# UpTo11_FrontPanel.net
KiCad netlist of a schematic drawn in EAGLE
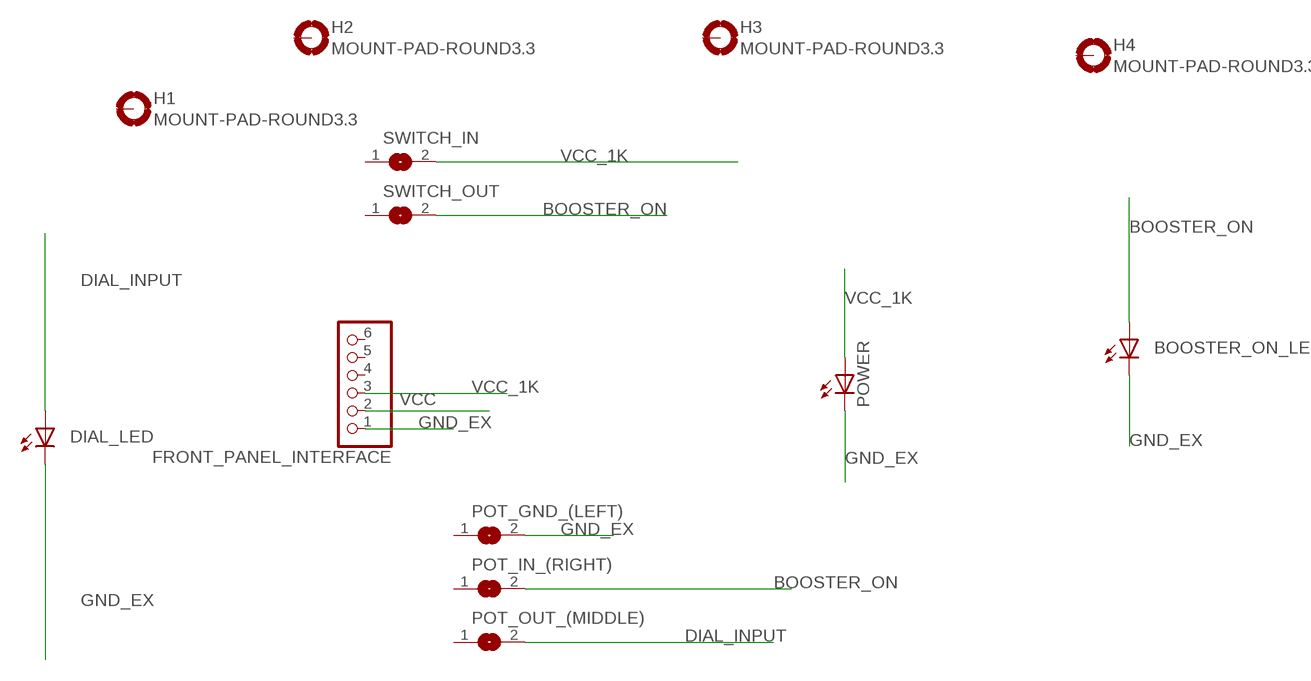
[diagram p0: schematic, sheet 1]

(export (version "E")
  (design (tool "Eeschema 10.0.6"))
  (components
    (comp (ref "BOOSTER_ON_LED")
      (value "LED5MM")
      (footprint "eagle-import:LED5MM")
      (libsource (lib "eagle-import") (part "LED5MM"))
    )
    (comp (ref "DIAL_LED")
      (value "LED5MM")
      (footprint "eagle-import:LED5MM")
      (libsource (lib "eagle-import") (part "LED5MM"))
    )
    (comp (ref "FRONT_PANEL_INTERFACE")
      (value "PINHD-1X6")
      (footprint "eagle-import:1X06")
      (libsource (lib "eagle-import") (part "PINHD-1X6"))
    )
    (comp (ref "H1")
      (value "MOUNT-PAD-ROUND3.3")
      (footprint "eagle-import:3,3-PAD")
      (libsource (lib "eagle-import") (part "MOUNT-PAD-ROUND3.3"))
    )
    (comp (ref "H2")
      (value "MOUNT-PAD-ROUND3.3")
      (footprint "eagle-import:3,3-PAD")
      (libsource (lib "eagle-import") (part "MOUNT-PAD-ROUND3.3"))
    )
    (comp (ref "H3")
      (value "MOUNT-PAD-ROUND3.3")
      (footprint "eagle-import:3,3-PAD")
      (libsource (lib "eagle-import") (part "MOUNT-PAD-ROUND3.3"))
    )
    (comp (ref "H4")
      (value "MOUNT-PAD-ROUND3.3")
      (footprint "eagle-import:3,3-PAD")
      (libsource (lib "eagle-import") (part "MOUNT-PAD-ROUND3.3"))
    )
    (comp (ref "POT_GND_(LEFT)")
      (value "SOLDERJUMPERREFLOW")
      (footprint "eagle-import:SOLDERJUMPER_REFLOW")
      (libsource (lib "eagle-import") (part "SOLDERJUMPERREFLOW"))
    )
    (comp (ref "POT_IN_(RIGHT)")
      (value "SOLDERJUMPERREFLOW")
      (footprint "eagle-import:SOLDERJUMPER_REFLOW")
      (libsource (lib "eagle-import") (part "SOLDERJUMPERREFLOW"))
    )
    (comp (ref "POT_OUT_(MIDDLE)")
      (value "SOLDERJUMPERREFLOW")
      (footprint "eagle-import:SOLDERJUMPER_REFLOW")
      (libsource (lib "eagle-import") (part "SOLDERJUMPERREFLOW"))
    )
    (comp (ref "POWER")
      (value "LEDSMT1206")
      (footprint "eagle-import:1206")
      (libsource (lib "eagle-import") (part "LEDSMT1206"))
    )
    (comp (ref "SWITCH_IN")
      (value "SOLDERJUMPERREFLOW")
      (footprint "eagle-import:SOLDERJUMPER_REFLOW")
      (libsource (lib "eagle-import") (part "SOLDERJUMPERREFLOW"))
    )
    (comp (ref "SWITCH_OUT")
      (value "SOLDERJUMPERREFLOW")
      (footprint "eagle-import:SOLDERJUMPER_REFLOW")
      (libsource (lib "eagle-import") (part "SOLDERJUMPERREFLOW"))
    )
  )
  (nets
    (net (code "1") (name "/BOOSTER_ON") (class "Default")
      (node (ref "BOOSTER_ON_LED") (pin "A") (pinfunction "A_A") (pintype "passive"))
      (node (ref "POT_IN_(RIGHT)") (pin "2") (pinfunction "2_2") (pintype "passive"))
      (node (ref "SWITCH_OUT") (pin "2") (pinfunction "2_2") (pintype "passive"))
    )
    (net (code "2") (name "/DIAL_INPUT") (class "Default")
      (node (ref "DIAL_LED") (pin "A") (pinfunction "A_A") (pintype "passive"))
      (node (ref "POT_OUT_(MIDDLE)") (pin "2") (pinfunction "2_2") (pintype "passive"))
    )
    (net (code "3") (name "/GND_EX") (class "Default")
      (node (ref "BOOSTER_ON_LED") (pin "K") (pinfunction "C_K") (pintype "passive"))
      (node (ref "DIAL_LED") (pin "K") (pinfunction "C_K") (pintype "passive"))
      (node (ref "FRONT_PANEL_INTERFACE") (pin "1") (pinfunction "1_1") (pintype "passive"))
      (node (ref "POT_GND_(LEFT)") (pin "2") (pinfunction "2_2") (pintype "passive"))
      (node (ref "POWER") (pin "C") (pinfunction "C_C") (pintype "passive"))
    )
    (net (code "4") (name "/VCC") (class "Default")
      (node (ref "FRONT_PANEL_INTERFACE") (pin "2") (pinfunction "2_2") (pintype "passive"))
    )
    (net (code "5") (name "/VCC_1K") (class "Default")
      (node (ref "FRONT_PANEL_INTERFACE") (pin "3") (pinfunction "3_3") (pintype "passive"))
      (node (ref "POWER") (pin "A") (pinfunction "A_A") (pintype "passive"))
      (node (ref "SWITCH_IN") (pin "2") (pinfunction "2_2") (pintype "passive"))
    )
    (net (code "6") (name "unconnected-(FRONT_PANEL_INTERFACE-Pad4)") (class "Default")
      (node (ref "FRONT_PANEL_INTERFACE") (pin "4") (pinfunction "4_4") (pintype "passive"))
    )
    (net (code "7") (name "unconnected-(FRONT_PANEL_INTERFACE-Pad5)") (class "Default")
      (node (ref "FRONT_PANEL_INTERFACE") (pin "5") (pinfunction "5_5") (pintype "passive"))
    )
    (net (code "8") (name "unconnected-(FRONT_PANEL_INTERFACE-Pad6)") (class "Default")
      (node (ref "FRONT_PANEL_INTERFACE") (pin "6") (pinfunction "6_6") (pintype "passive"))
    )
    (net (code "9") (name "unconnected-(H1-MOUNT-PadB3,3)") (class "Default")
      (node (ref "H1") (pin "B3,3") (pinfunction "MOUNT_B3,3") (pintype "passive"))
    )
    (net (code "10") (name "unconnected-(H2-MOUNT-PadB3,3)") (class "Default")
      (node (ref "H2") (pin "B3,3") (pinfunction "MOUNT_B3,3") (pintype "passive"))
    )
    (net (code "11") (name "unconnected-(H3-MOUNT-PadB3,3)") (class "Default")
      (node (ref "H3") (pin "B3,3") (pinfunction "MOUNT_B3,3") (pintype "passive"))
    )
    (net (code "12") (name "unconnected-(H4-MOUNT-PadB3,3)") (class "Default")
      (node (ref "H4") (pin "B3,3") (pinfunction "MOUNT_B3,3") (pintype "passive"))
    )
    (net (code "13") (name "unconnected-(POT_GND_(LEFT)-Pad1)") (class "Default")
      (node (ref "POT_GND_(LEFT)") (pin "1") (pinfunction "1_1") (pintype "passive"))
    )
    (net (code "14") (name "unconnected-(POT_IN_(RIGHT)-Pad1)") (class "Default")
      (node (ref "POT_IN_(RIGHT)") (pin "1") (pinfunction "1_1") (pintype "passive"))
    )
    (net (code "15") (name "unconnected-(POT_OUT_(MIDDLE)-Pad1)") (class "Default")
      (node (ref "POT_OUT_(MIDDLE)") (pin "1") (pinfunction "1_1") (pintype "passive"))
    )
    (net (code "16") (name "unconnected-(SWITCH_IN-Pad1)") (class "Default")
      (node (ref "SWITCH_IN") (pin "1") (pinfunction "1_1") (pintype "passive"))
    )
    (net (code "17") (name "unconnected-(SWITCH_OUT-Pad1)") (class "Default")
      (node (ref "SWITCH_OUT") (pin "1") (pinfunction "1_1") (pintype "passive"))
    )
  )
)
